# Cover.net
KiCad netlist of a schematic drawn in Altium Designer
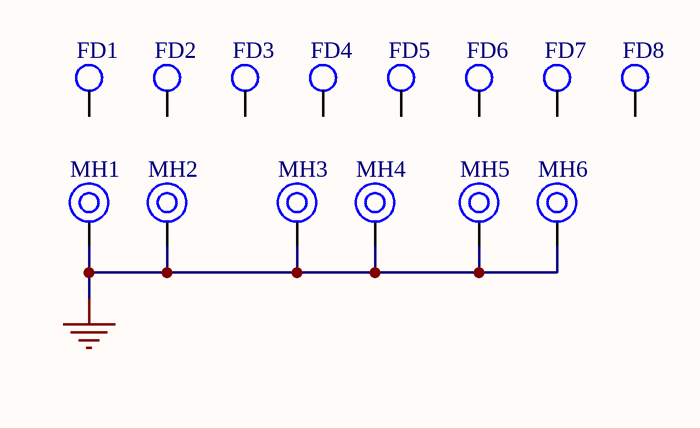
[diagram p0: Cover.SchDoc]

(export (version "E")
  (design (tool "Eeschema 10.0.6"))
  (components
    (comp (ref "FD1")
      (value "Fiducial")
      (footprint "FIDUCIAL_50MIL")
      (description "78.7 or 50 mil Fiducials SMD")
      (fields (field (name "MANUFACTURER") "NA"))
      (libsource (lib "EsteemPCB_SOM_Course_intlib") (part "Fiducials"))
    )
    (comp (ref "FD2")
      (value "Fiducial")
      (footprint "FIDUCIAL_50MIL")
      (description "78.7 or 50 mil Fiducials SMD")
      (fields (field (name "MANUFACTURER") "NA"))
      (libsource (lib "EsteemPCB_SOM_Course_intlib") (part "Fiducials"))
    )
    (comp (ref "FD3")
      (value "Fiducial")
      (footprint "FIDUCIAL_50MIL")
      (description "78.7 or 50 mil Fiducials SMD")
      (fields (field (name "MANUFACTURER") "NA"))
      (libsource (lib "EsteemPCB_SOM_Course_intlib") (part "Fiducials"))
    )
    (comp (ref "FD4")
      (value "Fiducial")
      (footprint "FIDUCIAL_50MIL")
      (description "78.7 or 50 mil Fiducials SMD")
      (fields (field (name "MANUFACTURER") "NA"))
      (libsource (lib "EsteemPCB_SOM_Course_intlib") (part "Fiducials"))
    )
    (comp (ref "FD5")
      (value "Fiducial")
      (footprint "FIDUCIAL_50MIL")
      (description "78.7 or 50 mil Fiducials SMD")
      (fields (field (name "MANUFACTURER") "NA"))
      (libsource (lib "EsteemPCB_SOM_Course_intlib") (part "Fiducials"))
    )
    (comp (ref "FD6")
      (value "Fiducial")
      (footprint "FIDUCIAL_50MIL")
      (description "78.7 or 50 mil Fiducials SMD")
      (fields (field (name "MANUFACTURER") "NA"))
      (libsource (lib "EsteemPCB_SOM_Course_intlib") (part "Fiducials"))
    )
    (comp (ref "FD7")
      (value "Fiducial")
      (footprint "FIDUCIAL_50MIL")
      (description "78.7 or 50 mil Fiducials SMD")
      (fields (field (name "MANUFACTURER") "NA"))
      (libsource (lib "EsteemPCB_SOM_Course_intlib") (part "Fiducials"))
    )
    (comp (ref "FD8")
      (value "Fiducial")
      (footprint "FIDUCIAL_50MIL")
      (description "78.7 or 50 mil Fiducials SMD")
      (fields (field (name "MANUFACTURER") "NA"))
      (libsource (lib "EsteemPCB_SOM_Course_intlib") (part "Fiducials"))
    )
    (comp (ref "MH1")
      (value "Mounting Hole")
      (footprint "SOM_Mounting")
      (fields (field (name "MANUFACTURER PART NUMBER") "NA"))
      (libsource (lib "EsteemPCB_SOM_Course_intlib") (part "MH_3.5H_6D"))
    )
    (comp (ref "MH2")
      (value "Mounting Hole")
      (footprint "SOM_Mounting")
      (fields (field (name "MANUFACTURER PART NUMBER") "NA"))
      (libsource (lib "EsteemPCB_SOM_Course_intlib") (part "MH_3.5H_6D"))
    )
    (comp (ref "MH3")
      (value "Mounting Hole")
      (footprint "SOM_Mounting")
      (fields (field (name "MANUFACTURER PART NUMBER") "NA"))
      (libsource (lib "EsteemPCB_SOM_Course_intlib") (part "MH_3.5H_6D"))
    )
    (comp (ref "MH4")
      (value "Mounting Hole")
      (footprint "SOM_Mounting")
      (fields (field (name "MANUFACTURER PART NUMBER") "NA"))
      (libsource (lib "EsteemPCB_SOM_Course_intlib") (part "MH_3.5H_6D"))
    )
    (comp (ref "MH5")
      (value "Mounting Hole")
      (footprint "SOM_Mounting")
      (fields (field (name "MANUFACTURER PART NUMBER") "NA"))
      (libsource (lib "EsteemPCB_SOM_Course_intlib") (part "MH_3.5H_6D"))
    )
    (comp (ref "MH6")
      (value "Mounting Hole")
      (footprint "SOM_Mounting")
      (fields (field (name "MANUFACTURER PART NUMBER") "NA"))
      (libsource (lib "EsteemPCB_SOM_Course_intlib") (part "MH_3.5H_6D"))
    )
  )
  (nets
    (net (code "1") (name "GND") (class "Default")
      (node (ref "MH1") (pin "1") (pinfunction "1_1") (pintype "passive"))
      (node (ref "MH2") (pin "1") (pinfunction "1_1") (pintype "passive"))
      (node (ref "MH3") (pin "1") (pinfunction "1_1") (pintype "passive"))
      (node (ref "MH4") (pin "1") (pinfunction "1_1") (pintype "passive"))
      (node (ref "MH5") (pin "1") (pinfunction "1_1") (pintype "passive"))
      (node (ref "MH6") (pin "1") (pinfunction "1_1") (pintype "passive"))
    )
    (net (code "2") (name "unconnected-(FD1-Pad1)") (class "Default")
      (node (ref "FD1") (pin "1") (pinfunction "1_1") (pintype "passive"))
    )
    (net (code "3") (name "unconnected-(FD2-Pad1)") (class "Default")
      (node (ref "FD2") (pin "1") (pinfunction "1_1") (pintype "passive"))
    )
    (net (code "4") (name "unconnected-(FD3-Pad1)") (class "Default")
      (node (ref "FD3") (pin "1") (pinfunction "1_1") (pintype "passive"))
    )
    (net (code "5") (name "unconnected-(FD4-Pad1)") (class "Default")
      (node (ref "FD4") (pin "1") (pinfunction "1_1") (pintype "passive"))
    )
    (net (code "6") (name "unconnected-(FD5-Pad1)") (class "Default")
      (node (ref "FD5") (pin "1") (pinfunction "1_1") (pintype "passive"))
    )
    (net (code "7") (name "unconnected-(FD6-Pad1)") (class "Default")
      (node (ref "FD6") (pin "1") (pinfunction "1_1") (pintype "passive"))
    )
    (net (code "8") (name "unconnected-(FD7-Pad1)") (class "Default")
      (node (ref "FD7") (pin "1") (pinfunction "1_1") (pintype "passive"))
    )
    (net (code "9") (name "unconnected-(FD8-Pad1)") (class "Default")
      (node (ref "FD8") (pin "1") (pinfunction "1_1") (pintype "passive"))
    )
  )
)
